# Feather_RTD_-_X9EG.net
KiCad netlist of a schematic drawn in EAGLE
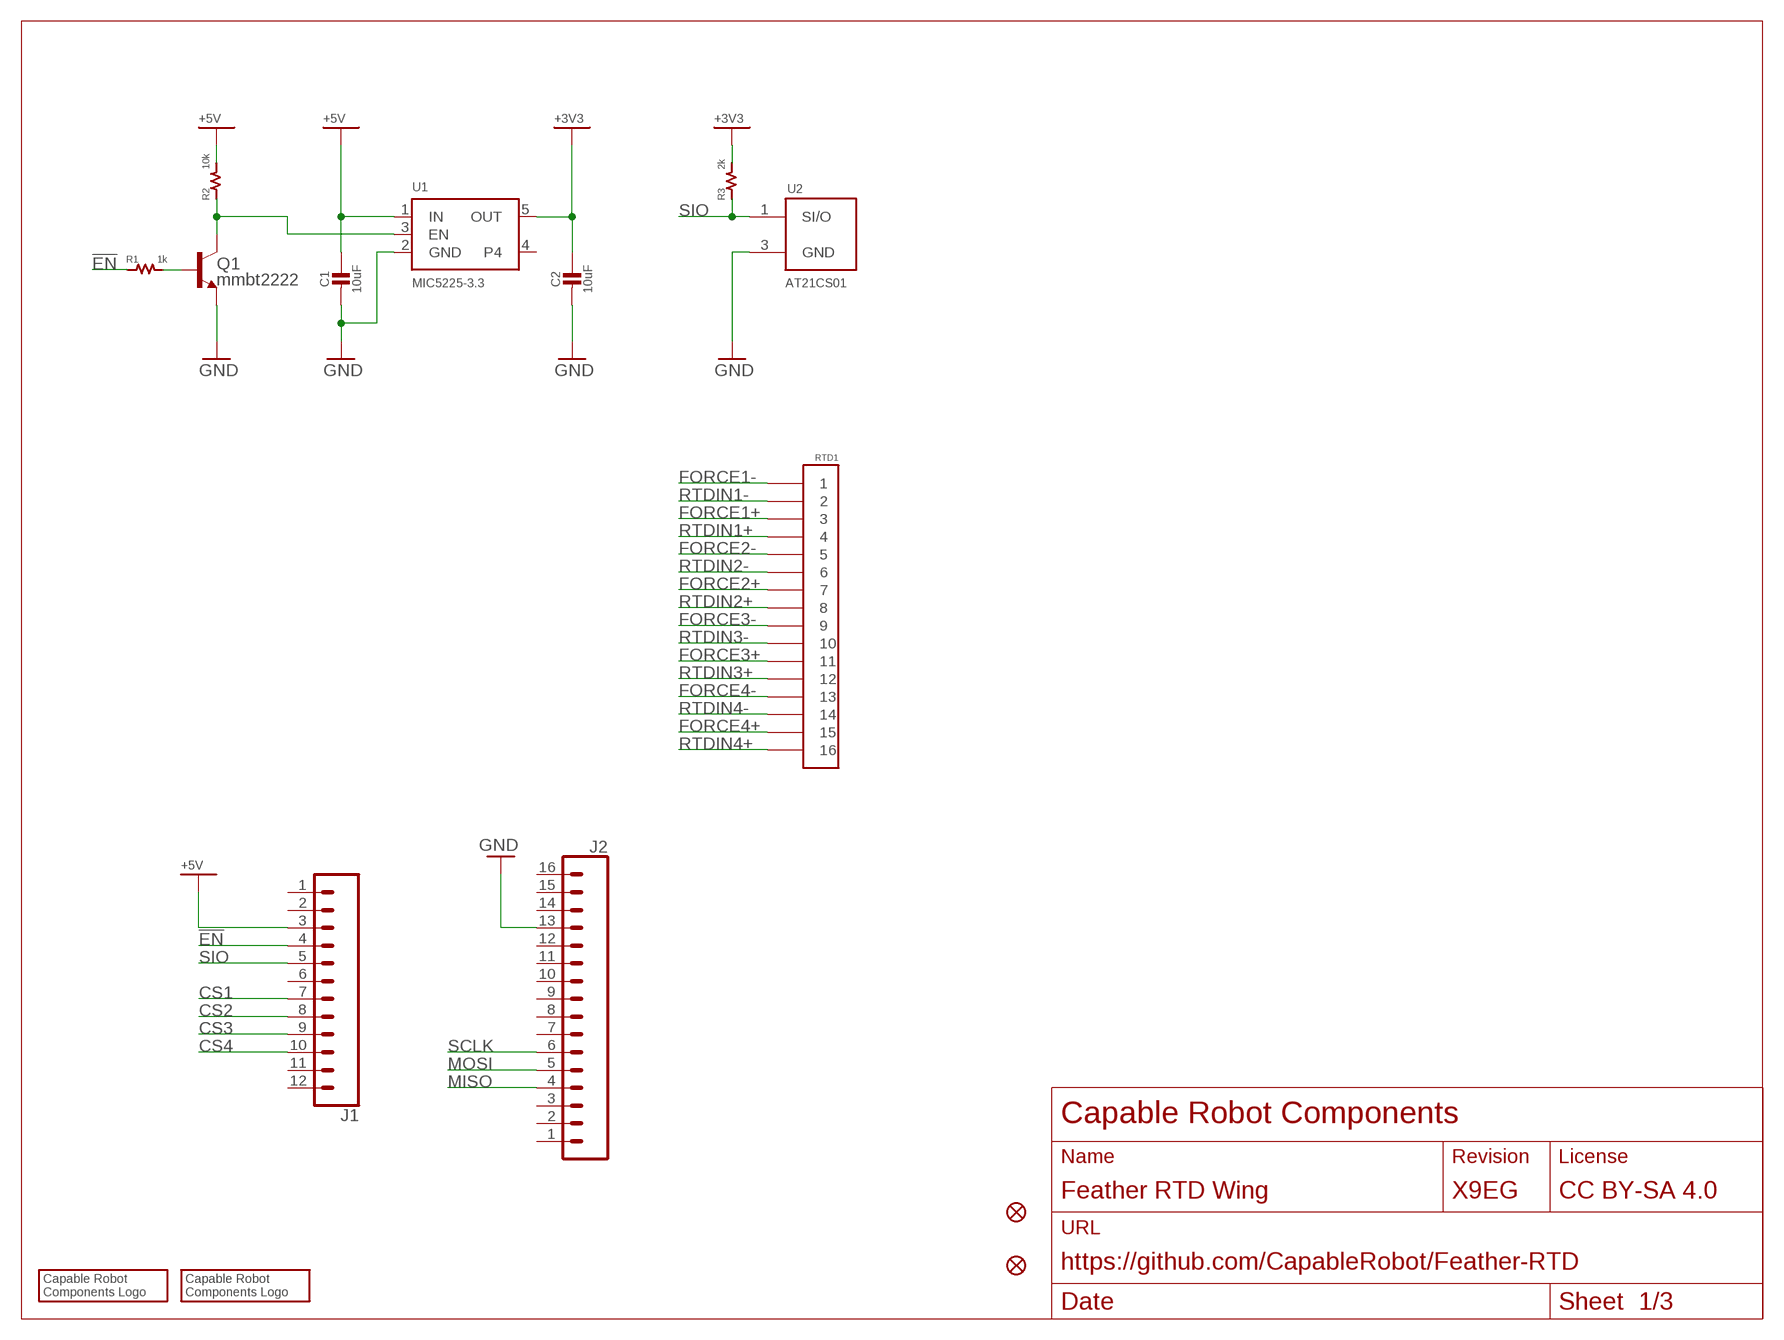
[diagram p0: schematic, sheet 1]
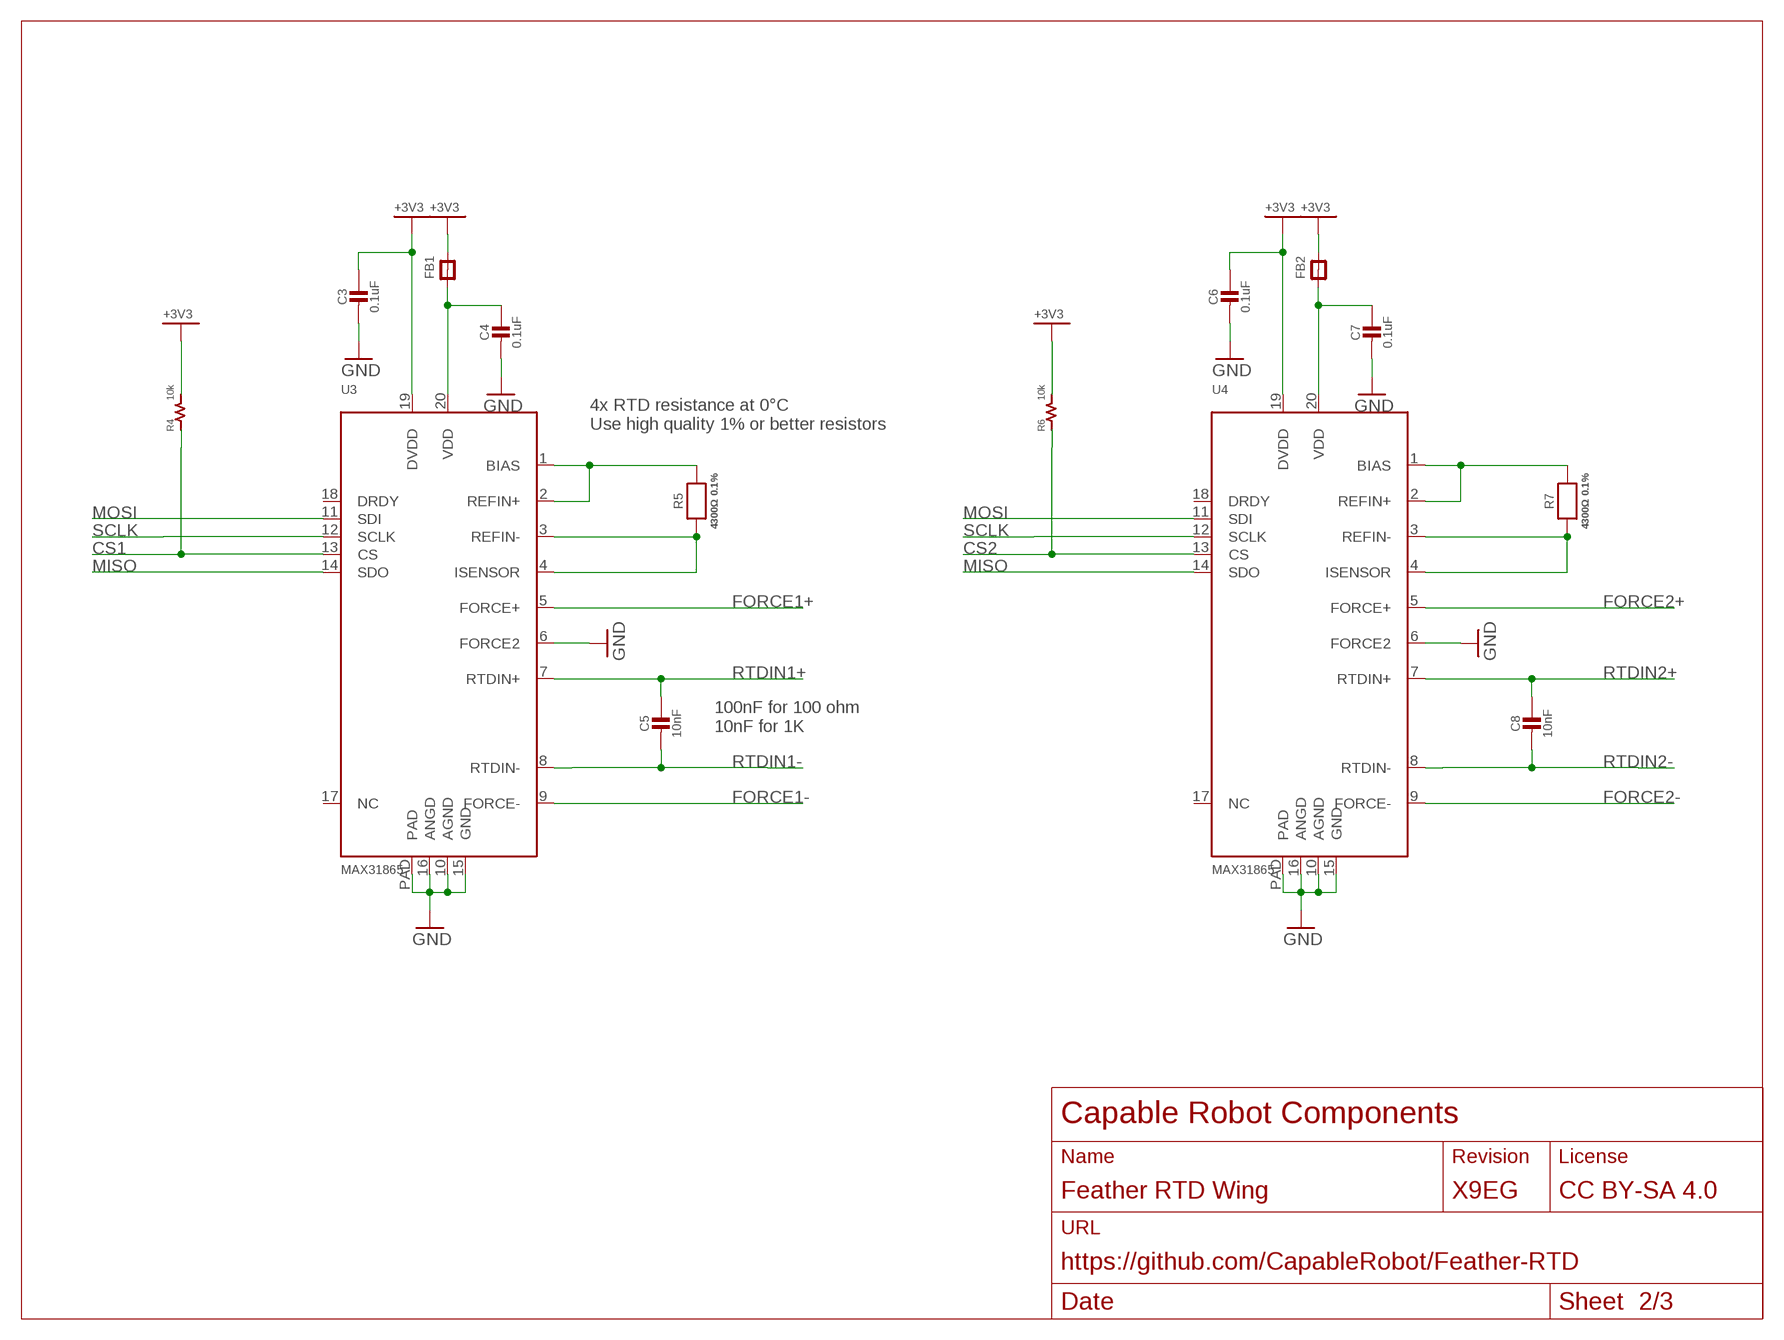
[diagram p1: schematic, sheet 2]
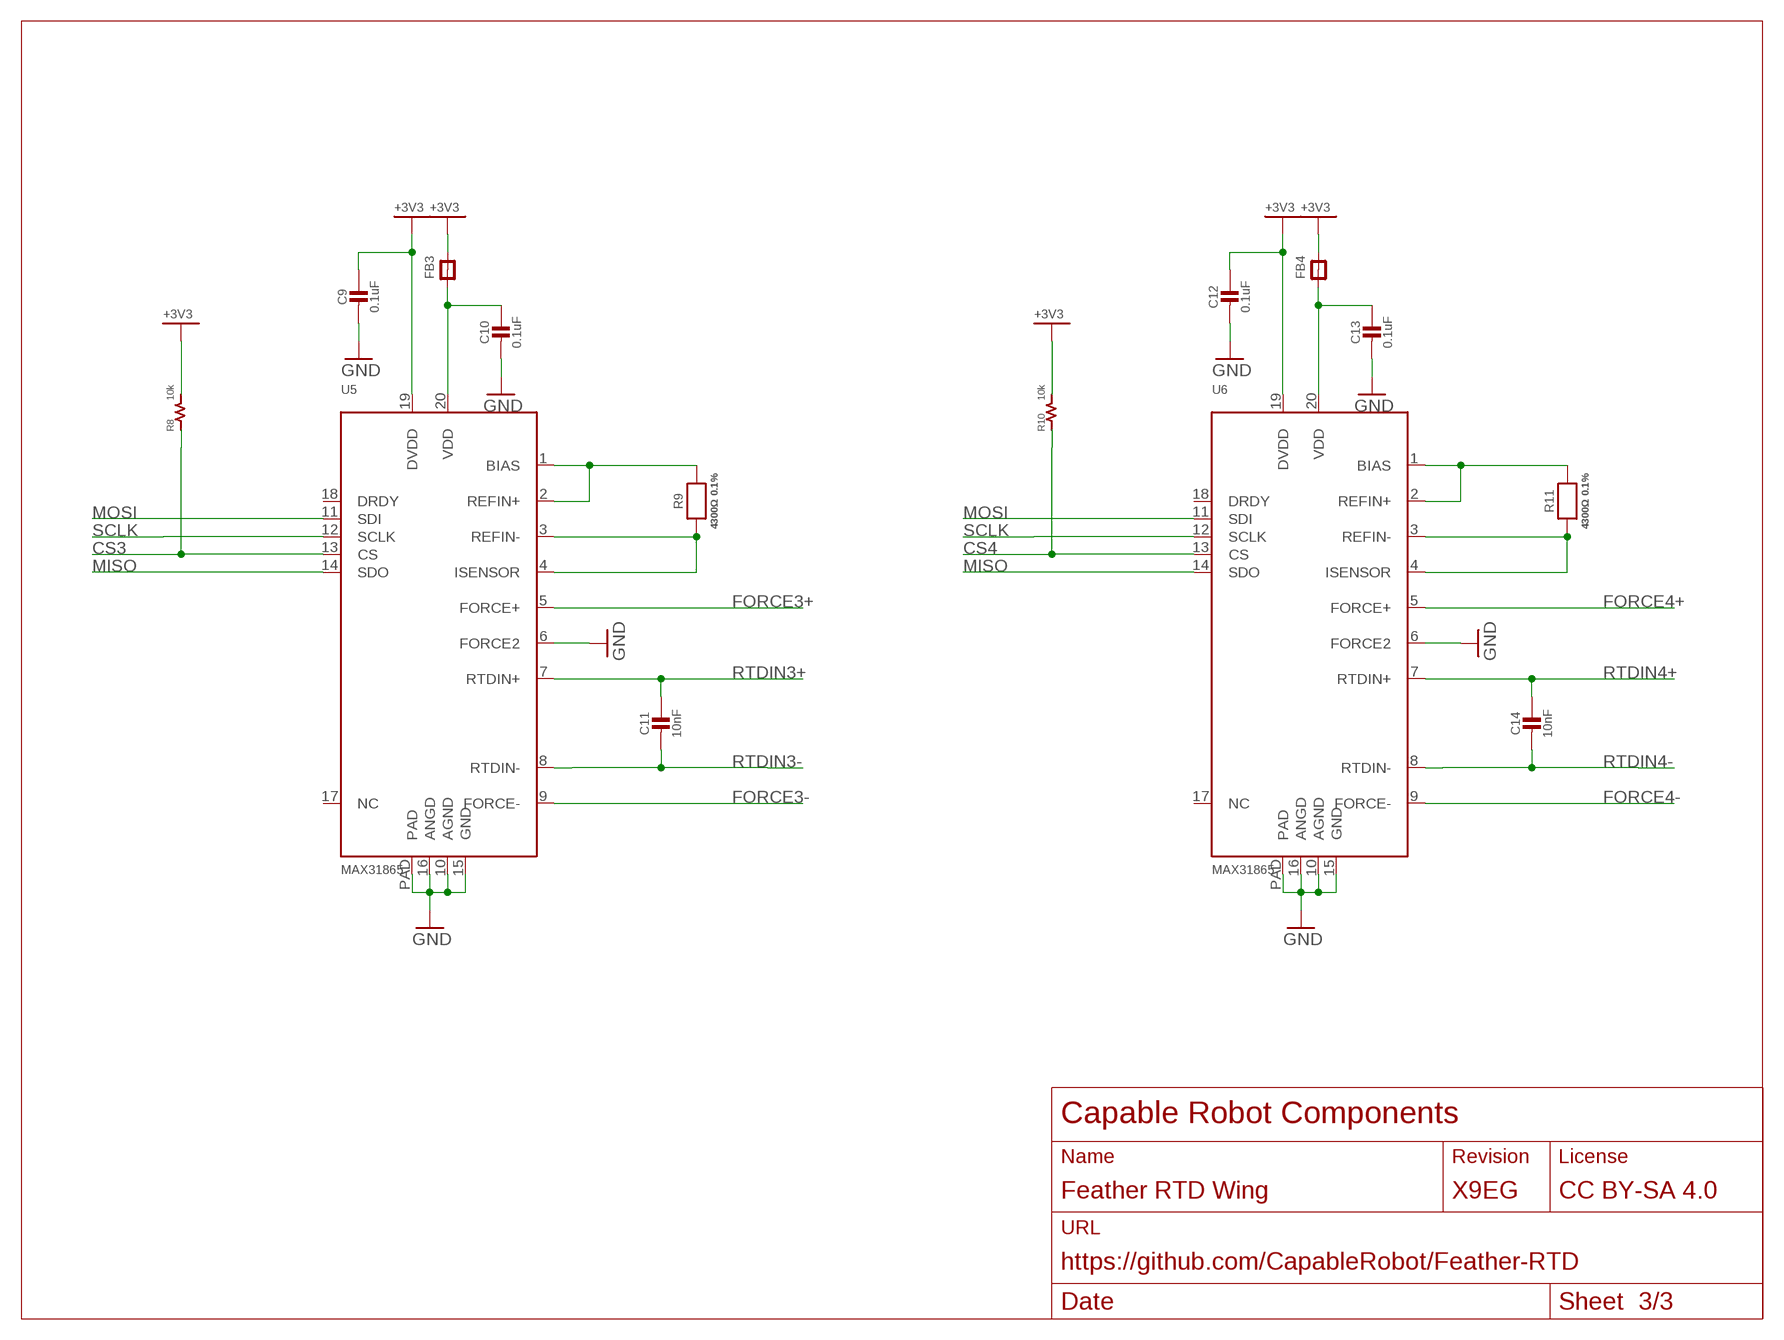
[diagram p2: schematic, sheet 3]

(export (version "E")
  (design (tool "Eeschema 10.0.6"))
  (components
    (comp (ref "C3")
      (value "0.1uF")
      (footprint "eagle-import:0805-NO")
      (libsource (lib "eagle-import") (part "CAP_CERAMIC0805-NOOUTLINE"))
    )
    (comp (ref "C4")
      (value "0.1uF")
      (footprint "eagle-import:0805-NO")
      (libsource (lib "eagle-import") (part "CAP_CERAMIC0805-NOOUTLINE"))
    )
    (comp (ref "C5")
      (value "10nF")
      (footprint "eagle-import:0805-NO")
      (libsource (lib "eagle-import") (part "CAP_CERAMIC0805-NOOUTLINE"))
    )
    (comp (ref "C6")
      (value "0.1uF")
      (footprint "eagle-import:0805-NO")
      (libsource (lib "eagle-import") (part "CAP_CERAMIC0805-NOOUTLINE"))
    )
    (comp (ref "C7")
      (value "0.1uF")
      (footprint "eagle-import:0805-NO")
      (libsource (lib "eagle-import") (part "CAP_CERAMIC0805-NOOUTLINE"))
    )
    (comp (ref "C8")
      (value "10nF")
      (footprint "eagle-import:0805-NO")
      (libsource (lib "eagle-import") (part "CAP_CERAMIC0805-NOOUTLINE"))
    )
    (comp (ref "FB1")
      (value "FERRITE-0805NO")
      (footprint "eagle-import:0805-NO")
      (libsource (lib "eagle-import") (part "FERRITE-0805NO"))
    )
    (comp (ref "FB2")
      (value "FERRITE-0805NO")
      (footprint "eagle-import:0805-NO")
      (libsource (lib "eagle-import") (part "FERRITE-0805NO"))
    )
    (comp (ref "R4")
      (value "10k")
      (footprint "eagle-import:0603")
      (libsource (lib "eagle-import") (part "RES0603"))
    )
    (comp (ref "R5")
      (value "4300Ω 0.1%")
      (footprint "eagle-import:0805-NO")
      (libsource (lib "eagle-import") (part "RESISTOR0805_NOOUTLINE"))
    )
    (comp (ref "R6")
      (value "10k")
      (footprint "eagle-import:0603")
      (libsource (lib "eagle-import") (part "RES0603"))
    )
    (comp (ref "R7")
      (value "4300Ω 0.1%")
      (footprint "eagle-import:0805-NO")
      (libsource (lib "eagle-import") (part "RESISTOR0805_NOOUTLINE"))
    )
    (comp (ref "U3")
      (value "MAX31865")
      (footprint "eagle-import:QFN20_4MM_0.65MM")
      (libsource (lib "eagle-import") (part "TEMP_MAX31865"))
    )
    (comp (ref "U4")
      (value "MAX31865")
      (footprint "eagle-import:QFN20_4MM_0.65MM")
      (libsource (lib "eagle-import") (part "TEMP_MAX31865"))
    )
    (comp (ref "C9")
      (value "0.1uF")
      (footprint "eagle-import:0805-NO")
      (libsource (lib "eagle-import") (part "CAP_CERAMIC0805-NOOUTLINE"))
    )
    (comp (ref "C10")
      (value "0.1uF")
      (footprint "eagle-import:0805-NO")
      (libsource (lib "eagle-import") (part "CAP_CERAMIC0805-NOOUTLINE"))
    )
    (comp (ref "C11")
      (value "10nF")
      (footprint "eagle-import:0805-NO")
      (libsource (lib "eagle-import") (part "CAP_CERAMIC0805-NOOUTLINE"))
    )
    (comp (ref "C12")
      (value "0.1uF")
      (footprint "eagle-import:0805-NO")
      (libsource (lib "eagle-import") (part "CAP_CERAMIC0805-NOOUTLINE"))
    )
    (comp (ref "C13")
      (value "0.1uF")
      (footprint "eagle-import:0805-NO")
      (libsource (lib "eagle-import") (part "CAP_CERAMIC0805-NOOUTLINE"))
    )
    (comp (ref "C14")
      (value "10nF")
      (footprint "eagle-import:0805-NO")
      (libsource (lib "eagle-import") (part "CAP_CERAMIC0805-NOOUTLINE"))
    )
    (comp (ref "FB3")
      (value "FERRITE-0805NO")
      (footprint "eagle-import:0805-NO")
      (libsource (lib "eagle-import") (part "FERRITE-0805NO"))
    )
    (comp (ref "FB4")
      (value "FERRITE-0805NO")
      (footprint "eagle-import:0805-NO")
      (libsource (lib "eagle-import") (part "FERRITE-0805NO"))
    )
    (comp (ref "R8")
      (value "10k")
      (footprint "eagle-import:0603")
      (libsource (lib "eagle-import") (part "RES0603"))
    )
    (comp (ref "R9")
      (value "4300Ω 0.1%")
      (footprint "eagle-import:0805-NO")
      (libsource (lib "eagle-import") (part "RESISTOR0805_NOOUTLINE"))
    )
    (comp (ref "R10")
      (value "10k")
      (footprint "eagle-import:0603")
      (libsource (lib "eagle-import") (part "RES0603"))
    )
    (comp (ref "R11")
      (value "4300Ω 0.1%")
      (footprint "eagle-import:0805-NO")
      (libsource (lib "eagle-import") (part "RESISTOR0805_NOOUTLINE"))
    )
    (comp (ref "U5")
      (value "MAX31865")
      (footprint "eagle-import:QFN20_4MM_0.65MM")
      (libsource (lib "eagle-import") (part "TEMP_MAX31865"))
    )
    (comp (ref "U6")
      (value "MAX31865")
      (footprint "eagle-import:QFN20_4MM_0.65MM")
      (libsource (lib "eagle-import") (part "TEMP_MAX31865"))
    )
    (comp (ref "C1")
      (value "10uF")
      (footprint "eagle-import:_1206")
      (libsource (lib "eagle-import") (part "CAP_CERAMIC_1206"))
    )
    (comp (ref "C2")
      (value "10uF")
      (footprint "eagle-import:_1206")
      (libsource (lib "eagle-import") (part "CAP_CERAMIC_1206"))
    )
    (comp (ref "FID1")
      (value "FIDUCIAL\"\"")
      (footprint "eagle-import:FIDUCIAL_1MM")
      (libsource (lib "eagle-import") (part "FIDUCIAL{dblquote}{dblquote}"))
    )
    (comp (ref "FID2")
      (value "FIDUCIAL\"\"")
      (footprint "eagle-import:FIDUCIAL_1MM")
      (libsource (lib "eagle-import") (part "FIDUCIAL{dblquote}{dblquote}"))
    )
    (comp (ref "J1")
      (value "CONN_12NO_SILK")
      (footprint "eagle-import:1X12_NO_SILK")
      (libsource (lib "eagle-import") (part "CONN_12NO_SILK"))
    )
    (comp (ref "J2")
      (value "CONN_161X16_NO_SILK")
      (footprint "eagle-import:1X16_NO_SILK")
      (libsource (lib "eagle-import") (part "CONN_161X16_NO_SILK"))
    )
    (comp (ref "LOGO1")
      (value "CRC-LOGO10")
      (footprint "eagle-import:CRC-LOGO-10")
      (libsource (lib "eagle-import") (part "CRC-LOGO10"))
    )
    (comp (ref "LOGO2")
      (value "CRC-LOGO5")
      (footprint "eagle-import:CRC-LOGO-5")
      (libsource (lib "eagle-import") (part "CRC-LOGO5"))
    )
    (comp (ref "Q1")
      (value "mmbt2222")
      (footprint "eagle-import:SOT23-3")
      (libsource (lib "eagle-import") (part "TRANS_NPN-MMBT2222AL"))
    )
    (comp (ref "R1")
      (value "1k")
      (footprint "eagle-import:0603")
      (libsource (lib "eagle-import") (part "CapableRobot_2153859_RES0603"))
    )
    (comp (ref "R2")
      (value "10k")
      (footprint "eagle-import:0603")
      (libsource (lib "eagle-import") (part "CapableRobot_2153859_RES0603"))
    )
    (comp (ref "R3")
      (value "2k")
      (footprint "eagle-import:0603")
      (libsource (lib "eagle-import") (part "CapableRobot_2153859_RES0603"))
    )
    (comp (ref "RTD1")
      (value "CONN-16ZT")
      (footprint "eagle-import:CONN-2X8-050-SMT-ZT")
      (libsource (lib "eagle-import") (part "CONN-16ZT"))
    )
    (comp (ref "U1")
      (value "MIC5225-3.3")
      (footprint "eagle-import:SOT23-5")
      (libsource (lib "eagle-import") (part "VREG_SOT23-5"))
    )
    (comp (ref "U2")
      (value "AT21CS01")
      (footprint "eagle-import:SOT23")
      (libsource (lib "eagle-import") (part "AT21CS01"))
    )
  )
  (nets
    (net (code "1") (name "+3V3") (class "Default")
      (node (ref "C12") (pin "1") (pinfunction "1_1") (pintype "passive"))
      (node (ref "C2") (pin "1") (pinfunction "1_1") (pintype "passive"))
      (node (ref "C3") (pin "1") (pinfunction "1_1") (pintype "passive"))
      (node (ref "C6") (pin "1") (pinfunction "1_1") (pintype "passive"))
      (node (ref "C9") (pin "1") (pinfunction "1_1") (pintype "passive"))
      (node (ref "FB1") (pin "2") (pinfunction "P$2_2") (pintype "passive"))
      (node (ref "FB2") (pin "2") (pinfunction "P$2_2") (pintype "passive"))
      (node (ref "FB3") (pin "2") (pinfunction "P$2_2") (pintype "passive"))
      (node (ref "FB4") (pin "2") (pinfunction "P$2_2") (pintype "passive"))
      (node (ref "R10") (pin "2") (pinfunction "2_2") (pintype "passive"))
      (node (ref "R3") (pin "2") (pinfunction "2_2") (pintype "passive"))
      (node (ref "R4") (pin "2") (pinfunction "2_2") (pintype "passive"))
      (node (ref "R6") (pin "2") (pinfunction "2_2") (pintype "passive"))
      (node (ref "R8") (pin "2") (pinfunction "2_2") (pintype "passive"))
      (node (ref "U1") (pin "5") (pinfunction "OUT_5") (pintype "power_in"))
      (node (ref "U3") (pin "19") (pinfunction "DVDD_19") (pintype "power_in"))
      (node (ref "U4") (pin "19") (pinfunction "DVDD_19") (pintype "power_in"))
      (node (ref "U5") (pin "19") (pinfunction "DVDD_19") (pintype "power_in"))
      (node (ref "U6") (pin "19") (pinfunction "DVDD_19") (pintype "power_in"))
    )
    (net (code "2") (name "+5V") (class "Default")
      (node (ref "C1") (pin "1") (pinfunction "1_1") (pintype "passive"))
      (node (ref "J1") (pin "3") (pinfunction "3_3") (pintype "passive"))
      (node (ref "R2") (pin "2") (pinfunction "2_2") (pintype "passive"))
      (node (ref "U1") (pin "1") (pinfunction "IN_1") (pintype "power_in"))
    )
    (net (code "3") (name "CS1") (class "Default")
      (node (ref "J1") (pin "7") (pinfunction "7_7") (pintype "passive"))
      (node (ref "R4") (pin "1") (pinfunction "1_1") (pintype "passive"))
      (node (ref "U3") (pin "13") (pinfunction "CS_13") (pintype "input"))
    )
    (net (code "4") (name "CS2") (class "Default")
      (node (ref "J1") (pin "8") (pinfunction "8_8") (pintype "passive"))
      (node (ref "R6") (pin "1") (pinfunction "1_1") (pintype "passive"))
      (node (ref "U4") (pin "13") (pinfunction "CS_13") (pintype "input"))
    )
    (net (code "5") (name "CS3") (class "Default")
      (node (ref "J1") (pin "9") (pinfunction "9_9") (pintype "passive"))
      (node (ref "R8") (pin "1") (pinfunction "1_1") (pintype "passive"))
      (node (ref "U5") (pin "13") (pinfunction "CS_13") (pintype "input"))
    )
    (net (code "6") (name "CS4") (class "Default")
      (node (ref "J1") (pin "10") (pinfunction "10_10") (pintype "passive"))
      (node (ref "R10") (pin "1") (pinfunction "1_1") (pintype "passive"))
      (node (ref "U6") (pin "13") (pinfunction "CS_13") (pintype "input"))
    )
    (net (code "7") (name "FORCE1+") (class "Default")
      (node (ref "RTD1") (pin "3") (pinfunction "3_3") (pintype "bidirectional"))
      (node (ref "U3") (pin "5") (pinfunction "FORCE+_5") (pintype "output"))
    )
    (net (code "8") (name "FORCE1-") (class "Default")
      (node (ref "RTD1") (pin "1") (pinfunction "1_1") (pintype "bidirectional"))
      (node (ref "U3") (pin "9") (pinfunction "FORCE-_9") (pintype "input"))
    )
    (net (code "9") (name "FORCE2+") (class "Default")
      (node (ref "RTD1") (pin "7") (pinfunction "7_7") (pintype "bidirectional"))
      (node (ref "U4") (pin "5") (pinfunction "FORCE+_5") (pintype "output"))
    )
    (net (code "10") (name "FORCE2-") (class "Default")
      (node (ref "RTD1") (pin "5") (pinfunction "5_5") (pintype "bidirectional"))
      (node (ref "U4") (pin "9") (pinfunction "FORCE-_9") (pintype "input"))
    )
    (net (code "11") (name "FORCE3+") (class "Default")
      (node (ref "RTD1") (pin "11") (pinfunction "11_11") (pintype "bidirectional"))
      (node (ref "U5") (pin "5") (pinfunction "FORCE+_5") (pintype "output"))
    )
    (net (code "12") (name "FORCE3-") (class "Default")
      (node (ref "RTD1") (pin "9") (pinfunction "9_9") (pintype "bidirectional"))
      (node (ref "U5") (pin "9") (pinfunction "FORCE-_9") (pintype "input"))
    )
    (net (code "13") (name "FORCE4+") (class "Default")
      (node (ref "RTD1") (pin "15") (pinfunction "15_15") (pintype "bidirectional"))
      (node (ref "U6") (pin "5") (pinfunction "FORCE+_5") (pintype "output"))
    )
    (net (code "14") (name "FORCE4-") (class "Default")
      (node (ref "RTD1") (pin "13") (pinfunction "13_13") (pintype "bidirectional"))
      (node (ref "U6") (pin "9") (pinfunction "FORCE-_9") (pintype "input"))
    )
    (net (code "15") (name "GND") (class "Default")
      (node (ref "C1") (pin "2") (pinfunction "2_2") (pintype "passive"))
      (node (ref "C10") (pin "2") (pinfunction "2_2") (pintype "passive"))
      (node (ref "C12") (pin "2") (pinfunction "2_2") (pintype "passive"))
      (node (ref "C13") (pin "2") (pinfunction "2_2") (pintype "passive"))
      (node (ref "C2") (pin "2") (pinfunction "2_2") (pintype "passive"))
      (node (ref "C3") (pin "2") (pinfunction "2_2") (pintype "passive"))
      (node (ref "C4") (pin "2") (pinfunction "2_2") (pintype "passive"))
      (node (ref "C6") (pin "2") (pinfunction "2_2") (pintype "passive"))
      (node (ref "C7") (pin "2") (pinfunction "2_2") (pintype "passive"))
      (node (ref "C9") (pin "2") (pinfunction "2_2") (pintype "passive"))
      (node (ref "J2") (pin "13") (pinfunction "13_13") (pintype "passive"))
      (node (ref "Q1") (pin "2") (pinfunction "E_2") (pintype "passive"))
      (node (ref "U1") (pin "2") (pinfunction "GND_2") (pintype "power_in"))
      (node (ref "U2") (pin "3") (pinfunction "GND_3") (pintype "bidirectional"))
      (node (ref "U3") (pin "10") (pinfunction "AGND_10") (pintype "power_in"))
      (node (ref "U3") (pin "15") (pinfunction "GND_15") (pintype "power_in"))
      (node (ref "U3") (pin "16") (pinfunction "ANGD_16") (pintype "power_in"))
      (node (ref "U3") (pin "6") (pinfunction "FORCE2_6") (pintype "bidirectional"))
      (node (ref "U3") (pin "PAD") (pinfunction "PAD_PAD") (pintype "power_in"))
      (node (ref "U4") (pin "10") (pinfunction "AGND_10") (pintype "power_in"))
      (node (ref "U4") (pin "15") (pinfunction "GND_15") (pintype "power_in"))
      (node (ref "U4") (pin "16") (pinfunction "ANGD_16") (pintype "power_in"))
      (node (ref "U4") (pin "6") (pinfunction "FORCE2_6") (pintype "bidirectional"))
      (node (ref "U4") (pin "PAD") (pinfunction "PAD_PAD") (pintype "power_in"))
      (node (ref "U5") (pin "10") (pinfunction "AGND_10") (pintype "power_in"))
      (node (ref "U5") (pin "15") (pinfunction "GND_15") (pintype "power_in"))
      (node (ref "U5") (pin "16") (pinfunction "ANGD_16") (pintype "power_in"))
      (node (ref "U5") (pin "6") (pinfunction "FORCE2_6") (pintype "bidirectional"))
      (node (ref "U5") (pin "PAD") (pinfunction "PAD_PAD") (pintype "power_in"))
      (node (ref "U6") (pin "10") (pinfunction "AGND_10") (pintype "power_in"))
      (node (ref "U6") (pin "15") (pinfunction "GND_15") (pintype "power_in"))
      (node (ref "U6") (pin "16") (pinfunction "ANGD_16") (pintype "power_in"))
      (node (ref "U6") (pin "6") (pinfunction "FORCE2_6") (pintype "bidirectional"))
      (node (ref "U6") (pin "PAD") (pinfunction "PAD_PAD") (pintype "power_in"))
    )
    (net (code "16") (name "MISO") (class "Default")
      (node (ref "J2") (pin "4") (pinfunction "4_4") (pintype "passive"))
      (node (ref "U3") (pin "14") (pinfunction "SDO_14") (pintype "output"))
      (node (ref "U4") (pin "14") (pinfunction "SDO_14") (pintype "output"))
      (node (ref "U5") (pin "14") (pinfunction "SDO_14") (pintype "output"))
      (node (ref "U6") (pin "14") (pinfunction "SDO_14") (pintype "output"))
    )
    (net (code "17") (name "MOSI") (class "Default")
      (node (ref "J2") (pin "5") (pinfunction "5_5") (pintype "passive"))
      (node (ref "U3") (pin "11") (pinfunction "SDI_11") (pintype "input"))
      (node (ref "U4") (pin "11") (pinfunction "SDI_11") (pintype "input"))
      (node (ref "U5") (pin "11") (pinfunction "SDI_11") (pintype "input"))
      (node (ref "U6") (pin "11") (pinfunction "SDI_11") (pintype "input"))
    )
    (net (code "18") (name "Net-(FB1-P$1)") (class "Default")
      (node (ref "C4") (pin "1") (pinfunction "1_1") (pintype "passive"))
      (node (ref "FB1") (pin "1") (pinfunction "P$1_1") (pintype "passive"))
      (node (ref "U3") (pin "20") (pinfunction "VDD_20") (pintype "power_in"))
    )
    (net (code "19") (name "Net-(FB2-P$1)") (class "Default")
      (node (ref "C7") (pin "1") (pinfunction "1_1") (pintype "passive"))
      (node (ref "FB2") (pin "1") (pinfunction "P$1_1") (pintype "passive"))
      (node (ref "U4") (pin "20") (pinfunction "VDD_20") (pintype "power_in"))
    )
    (net (code "20") (name "Net-(FB3-P$1)") (class "Default")
      (node (ref "C10") (pin "1") (pinfunction "1_1") (pintype "passive"))
      (node (ref "FB3") (pin "1") (pinfunction "P$1_1") (pintype "passive"))
      (node (ref "U5") (pin "20") (pinfunction "VDD_20") (pintype "power_in"))
    )
    (net (code "21") (name "Net-(FB4-P$1)") (class "Default")
      (node (ref "C13") (pin "1") (pinfunction "1_1") (pintype "passive"))
      (node (ref "FB4") (pin "1") (pinfunction "P$1_1") (pintype "passive"))
      (node (ref "U6") (pin "20") (pinfunction "VDD_20") (pintype "power_in"))
    )
    (net (code "22") (name "Net-(Q1-B)") (class "Default")
      (node (ref "Q1") (pin "1") (pinfunction "B_1") (pintype "passive"))
      (node (ref "R1") (pin "2") (pinfunction "2_2") (pintype "passive"))
    )
    (net (code "23") (name "Net-(Q1-C)") (class "Default")
      (node (ref "Q1") (pin "3") (pinfunction "C_3") (pintype "passive"))
      (node (ref "R2") (pin "1") (pinfunction "1_1") (pintype "passive"))
      (node (ref "U1") (pin "3") (pinfunction "EN_3") (pintype "input"))
    )
    (net (code "24") (name "Net-(U3-BIAS)") (class "Default")
      (node (ref "R5") (pin "2") (pinfunction "2_2") (pintype "passive"))
      (node (ref "U3") (pin "1") (pinfunction "BIAS_1") (pintype "output"))
      (node (ref "U3") (pin "2") (pinfunction "REFIN+_2") (pintype "bidirectional"))
    )
    (net (code "25") (name "Net-(U3-ISENSOR)") (class "Default")
      (node (ref "R5") (pin "1") (pinfunction "1_1") (pintype "passive"))
      (node (ref "U3") (pin "3") (pinfunction "REFIN-_3") (pintype "bidirectional"))
      (node (ref "U3") (pin "4") (pinfunction "ISENSOR_4") (pintype "input"))
    )
    (net (code "26") (name "Net-(U4-BIAS)") (class "Default")
      (node (ref "R7") (pin "2") (pinfunction "2_2") (pintype "passive"))
      (node (ref "U4") (pin "1") (pinfunction "BIAS_1") (pintype "output"))
      (node (ref "U4") (pin "2") (pinfunction "REFIN+_2") (pintype "bidirectional"))
    )
    (net (code "27") (name "Net-(U4-ISENSOR)") (class "Default")
      (node (ref "R7") (pin "1") (pinfunction "1_1") (pintype "passive"))
      (node (ref "U4") (pin "3") (pinfunction "REFIN-_3") (pintype "bidirectional"))
      (node (ref "U4") (pin "4") (pinfunction "ISENSOR_4") (pintype "input"))
    )
    (net (code "28") (name "Net-(U5-BIAS)") (class "Default")
      (node (ref "R9") (pin "2") (pinfunction "2_2") (pintype "passive"))
      (node (ref "U5") (pin "1") (pinfunction "BIAS_1") (pintype "output"))
      (node (ref "U5") (pin "2") (pinfunction "REFIN+_2") (pintype "bidirectional"))
    )
    (net (code "29") (name "Net-(U5-ISENSOR)") (class "Default")
      (node (ref "R9") (pin "1") (pinfunction "1_1") (pintype "passive"))
      (node (ref "U5") (pin "3") (pinfunction "REFIN-_3") (pintype "bidirectional"))
      (node (ref "U5") (pin "4") (pinfunction "ISENSOR_4") (pintype "input"))
    )
    (net (code "30") (name "Net-(U6-BIAS)") (class "Default")
      (node (ref "R11") (pin "2") (pinfunction "2_2") (pintype "passive"))
      (node (ref "U6") (pin "1") (pinfunction "BIAS_1") (pintype "output"))
      (node (ref "U6") (pin "2") (pinfunction "REFIN+_2") (pintype "bidirectional"))
    )
    (net (code "31") (name "Net-(U6-ISENSOR)") (class "Default")
      (node (ref "R11") (pin "1") (pinfunction "1_1") (pintype "passive"))
      (node (ref "U6") (pin "3") (pinfunction "REFIN-_3") (pintype "bidirectional"))
      (node (ref "U6") (pin "4") (pinfunction "ISENSOR_4") (pintype "input"))
    )
    (net (code "32") (name "RTDIN1+") (class "Default")
      (node (ref "C5") (pin "1") (pinfunction "1_1") (pintype "passive"))
      (node (ref "RTD1") (pin "4") (pinfunction "4_4") (pintype "bidirectional"))
      (node (ref "U3") (pin "7") (pinfunction "RTDIN+_7") (pintype "bidirectional"))
    )
    (net (code "33") (name "RTDIN1-") (class "Default")
      (node (ref "C5") (pin "2") (pinfunction "2_2") (pintype "passive"))
      (node (ref "RTD1") (pin "2") (pinfunction "2_2") (pintype "bidirectional"))
      (node (ref "U3") (pin "8") (pinfunction "RTDIN-_8") (pintype "bidirectional"))
    )
    (net (code "34") (name "RTDIN2+") (class "Default")
      (node (ref "C8") (pin "1") (pinfunction "1_1") (pintype "passive"))
      (node (ref "RTD1") (pin "8") (pinfunction "8_8") (pintype "bidirectional"))
      (node (ref "U4") (pin "7") (pinfunction "RTDIN+_7") (pintype "bidirectional"))
    )
    (net (code "35") (name "RTDIN2-") (class "Default")
      (node (ref "C8") (pin "2") (pinfunction "2_2") (pintype "passive"))
      (node (ref "RTD1") (pin "6") (pinfunction "6_6") (pintype "bidirectional"))
      (node (ref "U4") (pin "8") (pinfunction "RTDIN-_8") (pintype "bidirectional"))
    )
    (net (code "36") (name "RTDIN3+") (class "Default")
      (node (ref "C11") (pin "1") (pinfunction "1_1") (pintype "passive"))
      (node (ref "RTD1") (pin "12") (pinfunction "12_12") (pintype "bidirectional"))
      (node (ref "U5") (pin "7") (pinfunction "RTDIN+_7") (pintype "bidirectional"))
    )
    (net (code "37") (name "RTDIN3-") (class "Default")
      (node (ref "C11") (pin "2") (pinfunction "2_2") (pintype "passive"))
      (node (ref "RTD1") (pin "10") (pinfunction "10_10") (pintype "bidirectional"))
      (node (ref "U5") (pin "8") (pinfunction "RTDIN-_8") (pintype "bidirectional"))
    )
    (net (code "38") (name "RTDIN4+") (class "Default")
      (node (ref "C14") (pin "1") (pinfunction "1_1") (pintype "passive"))
      (node (ref "RTD1") (pin "16") (pinfunction "16_16") (pintype "bidirectional"))
      (node (ref "U6") (pin "7") (pinfunction "RTDIN+_7") (pintype "bidirectional"))
    )
    (net (code "39") (name "RTDIN4-") (class "Default")
      (node (ref "C14") (pin "2") (pinfunction "2_2") (pintype "passive"))
      (node (ref "RTD1") (pin "14") (pinfunction "14_14") (pintype "bidirectional"))
      (node (ref "U6") (pin "8") (pinfunction "RTDIN-_8") (pintype "bidirectional"))
    )
    (net (code "40") (name "SCLK") (class "Default")
      (node (ref "J2") (pin "6") (pinfunction "6_6") (pintype "passive"))
      (node (ref "U3") (pin "12") (pinfunction "SCLK_12") (pintype "input"))
      (node (ref "U4") (pin "12") (pinfunction "SCLK_12") (pintype "input"))
      (node (ref "U5") (pin "12") (pinfunction "SCLK_12") (pintype "input"))
      (node (ref "U6") (pin "12") (pinfunction "SCLK_12") (pintype "input"))
    )
    (net (code "41") (name "SIO") (class "Default")
      (node (ref "J1") (pin "5") (pinfunction "5_5") (pintype "passive"))
      (node (ref "R3") (pin "1") (pinfunction "1_1") (pintype "passive"))
      (node (ref "U2") (pin "1") (pinfunction "SI/O_1") (pintype "bidirectional"))
    )
    (net (code "42") (name "unconnected-(J1-Pad1)") (class "Default")
      (node (ref "J1") (pin "1") (pinfunction "1_1") (pintype "passive"))
    )
    (net (code "43") (name "unconnected-(J1-Pad2)") (class "Default")
      (node (ref "J1") (pin "2") (pinfunction "2_2") (pintype "passive"))
    )
    (net (code "44") (name "unconnected-(J1-Pad6)") (class "Default")
      (node (ref "J1") (pin "6") (pinfunction "6_6") (pintype "passive"))
    )
    (net (code "45") (name "unconnected-(J1-Pad11)") (class "Default")
      (node (ref "J1") (pin "11") (pinfunction "11_11") (pintype "passive"))
    )
    (net (code "46") (name "unconnected-(J1-Pad12)") (class "Default")
      (node (ref "J1") (pin "12") (pinfunction "12_12") (pintype "passive"))
    )
    (net (code "47") (name "unconnected-(J2-Pad1)") (class "Default")
      (node (ref "J2") (pin "1") (pinfunction "1_1") (pintype "passive"))
    )
    (net (code "48") (name "unconnected-(J2-Pad2)") (class "Default")
      (node (ref "J2") (pin "2") (pinfunction "2_2") (pintype "passive"))
    )
    (net (code "49") (name "unconnected-(J2-Pad3)") (class "Default")
      (node (ref "J2") (pin "3") (pinfunction "3_3") (pintype "passive"))
    )
    (net (code "50") (name "unconnected-(J2-Pad7)") (class "Default")
      (node (ref "J2") (pin "7") (pinfunction "7_7") (pintype "passive"))
    )
    (net (code "51") (name "unconnected-(J2-Pad8)") (class "Default")
      (node (ref "J2") (pin "8") (pinfunction "8_8") (pintype "passive"))
    )
    (net (code "52") (name "unconnected-(J2-Pad9)") (class "Default")
      (node (ref "J2") (pin "9") (pinfunction "9_9") (pintype "passive"))
    )
    (net (code "53") (name "unconnected-(J2-Pad10)") (class "Default")
      (node (ref "J2") (pin "10") (pinfunction "10_10") (pintype "passive"))
    )
    (net (code "54") (name "unconnected-(J2-Pad11)") (class "Default")
      (node (ref "J2") (pin "11") (pinfunction "11_11") (pintype "passive"))
    )
    (net (code "55") (name "unconnected-(J2-Pad12)") (class "Default")
      (node (ref "J2") (pin "12") (pinfunction "12_12") (pintype "passive"))
    )
    (net (code "56") (name "unconnected-(J2-Pad14)") (class "Default")
      (node (ref "J2") (pin "14") (pinfunction "14_14") (pintype "passive"))
    )
    (net (code "57") (name "unconnected-(J2-Pad15)") (class "Default")
      (node (ref "J2") (pin "15") (pinfunction "15_15") (pintype "passive"))
    )
    (net (code "58") (name "unconnected-(J2-Pad16)") (class "Default")
      (node (ref "J2") (pin "16") (pinfunction "16_16") (pintype "passive"))
    )
    (net (code "59") (name "unconnected-(U1-P4-Pad4)") (class "Default")
      (node (ref "U1") (pin "4") (pinfunction "P4_4") (pintype "bidirectional"))
    )
    (net (code "60") (name "unconnected-(U3-DRDY-Pad18)") (class "Default")
      (node (ref "U3") (pin "18") (pinfunction "DRDY_18") (pintype "output"))
    )
    (net (code "61") (name "unconnected-(U3-NC-Pad17)") (class "Default")
      (node (ref "U3") (pin "17") (pinfunction "NC_17") (pintype "no_connect"))
    )
    (net (code "62") (name "unconnected-(U4-DRDY-Pad18)") (class "Default")
      (node (ref "U4") (pin "18") (pinfunction "DRDY_18") (pintype "output"))
    )
    (net (code "63") (name "unconnected-(U4-NC-Pad17)") (class "Default")
      (node (ref "U4") (pin "17") (pinfunction "NC_17") (pintype "no_connect"))
    )
    (net (code "64") (name "unconnected-(U5-DRDY-Pad18)") (class "Default")
      (node (ref "U5") (pin "18") (pinfunction "DRDY_18") (pintype "output"))
    )
    (net (code "65") (name "unconnected-(U5-NC-Pad17)") (class "Default")
      (node (ref "U5") (pin "17") (pinfunction "NC_17") (pintype "no_connect"))
    )
    (net (code "66") (name "unconnected-(U6-DRDY-Pad18)") (class "Default")
      (node (ref "U6") (pin "18") (pinfunction "DRDY_18") (pintype "output"))
    )
    (net (code "67") (name "unconnected-(U6-NC-Pad17)") (class "Default")
      (node (ref "U6") (pin "17") (pinfunction "NC_17") (pintype "no_connect"))
    )
    (net (code "68") (name "~{EN}") (class "Default")
      (node (ref "J1") (pin "4") (pinfunction "4_4") (pintype "passive"))
      (node (ref "R1") (pin "1") (pinfunction "1_1") (pintype "passive"))
    )
  )
)
